# Block_Diagramme.net
KiCad netlist of a schematic drawn in Altium Designer
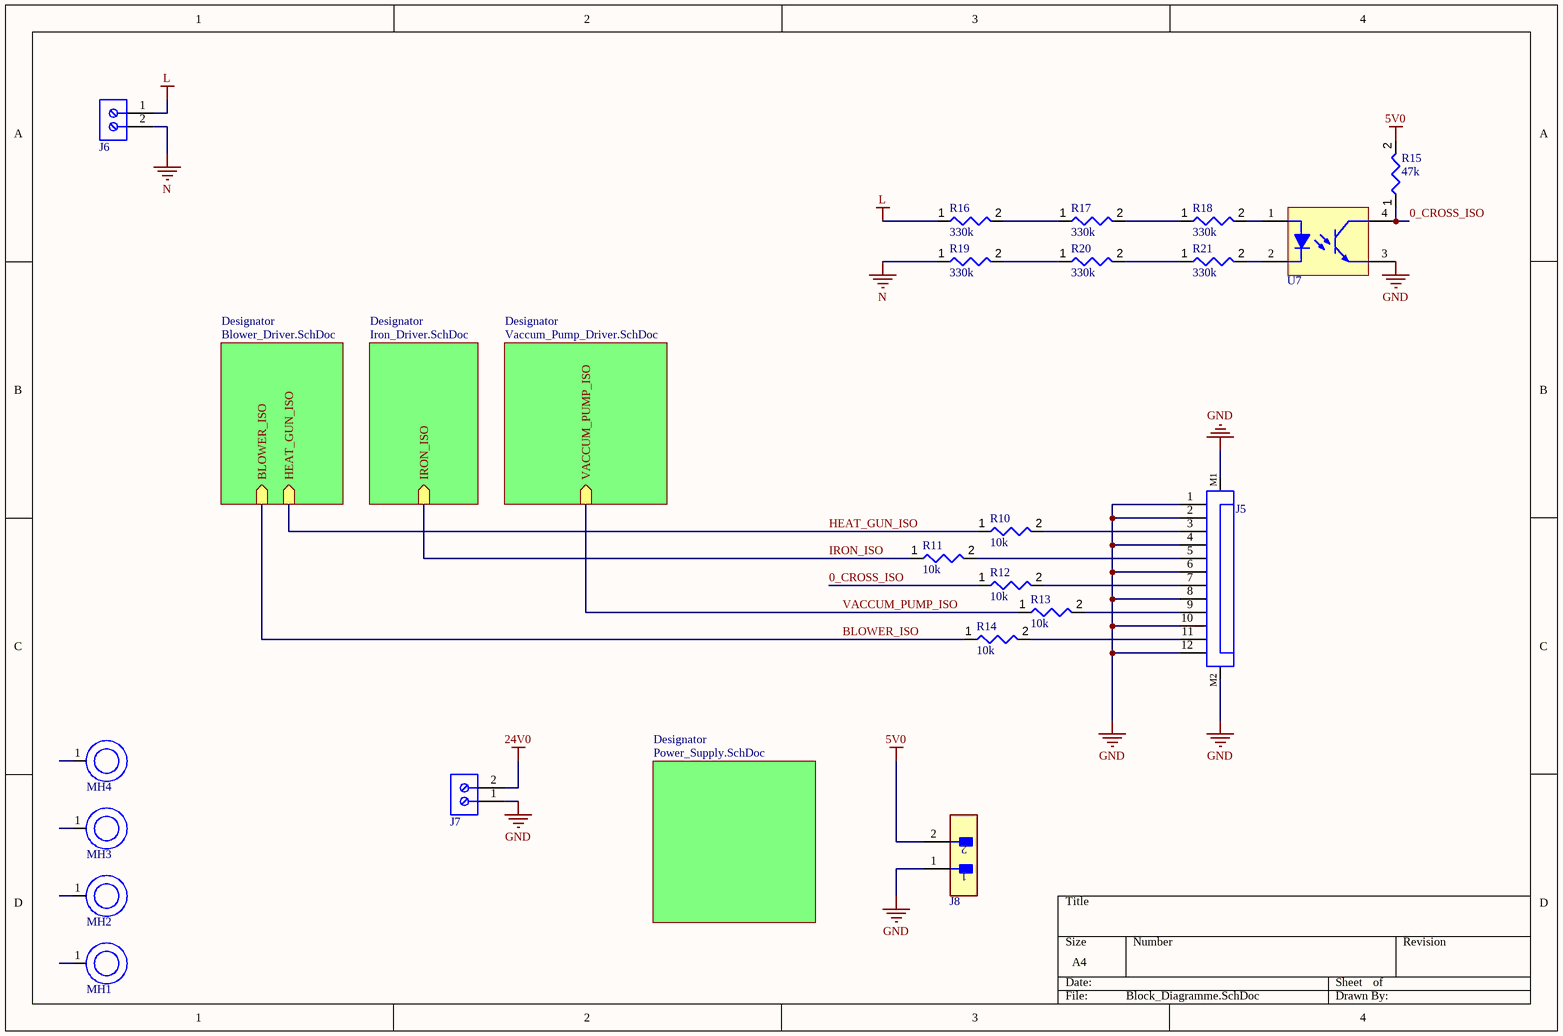
[diagram p0: Block_Diagramme.SchDoc]

(export (version "E")
  (design (tool "Eeschema 10.0.6"))
  (components
    (comp (ref "J5")
      (value "687112183622")
      (footprint "687112183622")
      (libsource (lib "Altium Content Vault") (part "FPC - 12P - 2MP"))
    )
    (comp (ref "J6")
      (value "691137710002")
      (footprint "691137710002")
      (description "2P Block Terminal")
      (libsource (lib "Paulo Peixoto") (part "Generic_2P_Block_Terminal"))
    )
    (comp (ref "J7")
      (value "691137710002")
      (footprint "691137710002")
      (description "2P Block Terminal")
      (libsource (lib "Paulo Peixoto") (part "Generic_2P_Block_Terminal"))
    )
    (comp (ref "J8")
      (value "B2B-XH-A(LF)(SN)")
      (footprint "FP-B2B-XH-A_LF_SN-MFG")
      (description "CONNECTOR HEADER, XH SERIES, 2 POSITION, 2.50MM, Press-Fit Solder, Detent Lock, Natural")
      (libsource (lib "Paulo Peixoto") (part "3bc925449376181038e59eaffc5286c"))
    )
    (comp (ref "MH1")
      (value "3mm_Mounting_Hole")
      (footprint "Single_3mm_Mounting_Hole")
      (description "3.2mm, sPad Mounting Hole")
      (libsource (lib "Paulo Peixoto") (part "Generic_Mounting_Hole"))
    )
    (comp (ref "MH2")
      (value "3mm_Mounting_Hole")
      (footprint "Single_3mm_Mounting_Hole")
      (description "3.2mm, sPad Mounting Hole")
      (libsource (lib "Paulo Peixoto") (part "Generic_Mounting_Hole"))
    )
    (comp (ref "MH3")
      (value "3mm_Mounting_Hole")
      (footprint "Single_3mm_Mounting_Hole")
      (description "3.2mm, sPad Mounting Hole")
      (libsource (lib "Paulo Peixoto") (part "Generic_Mounting_Hole"))
    )
    (comp (ref "MH4")
      (value "3mm_Mounting_Hole")
      (footprint "Single_3mm_Mounting_Hole")
      (description "3.2mm, sPad Mounting Hole")
      (libsource (lib "Paulo Peixoto") (part "Generic_Mounting_Hole"))
    )
    (comp (ref "R10")
      (value "10k")
      (footprint "Generic_0603_RES")
      (fields
        (field (name "TOLERANCE") "1%")
        (field (name "POWER") "100mW")
        (field (name "Comment") "RES-TK_SMD-0603_VIS-CRCW_K_10K_1/10W_1%")
      )
      (libsource (lib "Paulo Peixoto") (part "Res"))
    )
    (comp (ref "R11")
      (value "10k")
      (footprint "Generic_0603_RES")
      (fields
        (field (name "TOLERANCE") "1%")
        (field (name "POWER") "100mW")
        (field (name "Comment") "RES-TK_SMD-0603_VIS-CRCW_K_10K_1/10W_1%")
      )
      (libsource (lib "Paulo Peixoto") (part "Res"))
    )
    (comp (ref "R12")
      (value "10k")
      (footprint "Generic_0603_RES")
      (fields
        (field (name "TOLERANCE") "1%")
        (field (name "POWER") "100mW")
        (field (name "Comment") "RES-TK_SMD-0603_VIS-CRCW_K_10K_1/10W_1%")
      )
      (libsource (lib "Paulo Peixoto") (part "Res"))
    )
    (comp (ref "R13")
      (value "10k")
      (footprint "Generic_0603_RES")
      (fields
        (field (name "TOLERANCE") "1%")
        (field (name "POWER") "100mW")
        (field (name "Comment") "RES-TK_SMD-0603_VIS-CRCW_K_10K_1/10W_1%")
      )
      (libsource (lib "Paulo Peixoto") (part "Res"))
    )
    (comp (ref "R14")
      (value "10k")
      (footprint "Generic_0603_RES")
      (fields
        (field (name "TOLERANCE") "1%")
        (field (name "POWER") "100mW")
        (field (name "Comment") "RES-TK_SMD-0603_VIS-CRCW_K_10K_1/10W_1%")
      )
      (libsource (lib "Paulo Peixoto") (part "Res"))
    )
    (comp (ref "R15")
      (value "47k")
      (footprint "Generic_0603_RES")
      (fields
        (field (name "TOLERANCE") "1%")
        (field (name "POWER") "100mW")
        (field (name "Comment") "RES-TK_SMD-0603_VIS-CRCW_K_47K_1/10W_1%")
      )
      (libsource (lib "Paulo Peixoto") (part "Res"))
    )
    (comp (ref "R16")
      (value "330k")
      (footprint "Generic_1206_RES")
      (description "Res Thick Film 1206 330K Ohm 1% 1/4W ±100ppm/°C Molded SMD SMD Paper T/R")
      (fields (field (name "TOLERANCE") "1%") (field (name "POWER") "750mW"))
      (libsource (lib "Paulo Peixoto") (part "Res"))
    )
    (comp (ref "R17")
      (value "330k")
      (footprint "Generic_1206_RES")
      (description "Res Thick Film 1206 330K Ohm 1% 1/4W ±100ppm/°C Molded SMD SMD Paper T/R")
      (fields (field (name "TOLERANCE") "1%") (field (name "POWER") "750mW"))
      (libsource (lib "Paulo Peixoto") (part "Res"))
    )
    (comp (ref "R18")
      (value "330k")
      (footprint "Generic_1206_RES")
      (description "Res Thick Film 1206 330K Ohm 1% 1/4W ±100ppm/°C Molded SMD SMD Paper T/R")
      (fields (field (name "TOLERANCE") "1%") (field (name "POWER") "750mW"))
      (libsource (lib "Paulo Peixoto") (part "Res"))
    )
    (comp (ref "R19")
      (value "330k")
      (footprint "Generic_1206_RES")
      (description "Res Thick Film 1206 330K Ohm 1% 1/4W ±100ppm/°C Molded SMD SMD Paper T/R")
      (fields (field (name "TOLERANCE") "1%") (field (name "POWER") "750mW"))
      (libsource (lib "Paulo Peixoto") (part "Res"))
    )
    (comp (ref "R20")
      (value "330k")
      (footprint "Generic_1206_RES")
      (description "Res Thick Film 1206 330K Ohm 1% 1/4W ±100ppm/°C Molded SMD SMD Paper T/R")
      (fields (field (name "TOLERANCE") "1%") (field (name "POWER") "750mW"))
      (libsource (lib "Paulo Peixoto") (part "Res"))
    )
    (comp (ref "R21")
      (value "330k")
      (footprint "Generic_1206_RES")
      (description "Res Thick Film 1206 330K Ohm 1% 1/4W ±100ppm/°C Molded SMD SMD Paper T/R")
      (fields (field (name "TOLERANCE") "1%") (field (name "POWER") "750mW"))
      (libsource (lib "Paulo Peixoto") (part "Res"))
    )
    (comp (ref "U7")
      (value "H11A817ASD")
      (footprint "FAIR-H11A817ASD-4_V")
      (description "OptoCouplers & OptoIsolators Optocoupler SM-DIP4 Phototransistor")
      (libsource (lib "Paulo Peixoto") (part "FAIR-H11A817-4"))
    )
  )
  (nets
    (net (code "1") (name "/0_CROSS_ISO") (class "Default")
      (node (ref "R12") (pin "1") (pinfunction "1_1") (pintype "passive"))
      (node (ref "R15") (pin "1") (pinfunction "1_1") (pintype "passive"))
      (node (ref "U7") (pin "4") (pinfunction "COLLECTOR_4") (pintype "passive"))
    )
    (net (code "2") (name "/BLOWER_ISO") (class "Default")
      (node (ref "R14") (pin "1") (pinfunction "1_1") (pintype "passive"))
    )
    (net (code "3") (name "/HEAT_GUN_ISO") (class "Default")
      (node (ref "R10") (pin "1") (pinfunction "1_1") (pintype "passive"))
    )
    (net (code "4") (name "/IRON_ISO") (class "Default")
      (node (ref "R11") (pin "1") (pinfunction "1_1") (pintype "passive"))
    )
    (net (code "5") (name "/VACCUM_PUMP_ISO") (class "Default")
      (node (ref "R13") (pin "1") (pinfunction "1_1") (pintype "passive"))
    )
    (net (code "6") (name "5V0") (class "Default")
      (node (ref "J8") (pin "2") (pinfunction "2_2") (pintype "passive"))
      (node (ref "R15") (pin "2") (pinfunction "2_2") (pintype "passive"))
    )
    (net (code "7") (name "24V0") (class "Default")
      (node (ref "J7") (pin "2") (pinfunction "2_2") (pintype "passive"))
    )
    (net (code "8") (name "GND") (class "Default")
      (node (ref "J5") (pin "1") (pinfunction "1_1") (pintype "passive"))
      (node (ref "J5") (pin "10") (pinfunction "10_10") (pintype "passive"))
      (node (ref "J5") (pin "12") (pinfunction "12_12") (pintype "passive"))
      (node (ref "J5") (pin "2") (pinfunction "2_2") (pintype "passive"))
      (node (ref "J5") (pin "4") (pinfunction "4_4") (pintype "passive"))
      (node (ref "J5") (pin "6") (pinfunction "6_6") (pintype "passive"))
      (node (ref "J5") (pin "8") (pinfunction "8_8") (pintype "passive"))
      (node (ref "J5") (pin "M1") (pinfunction "M1_M1") (pintype "passive"))
      (node (ref "J5") (pin "M2") (pinfunction "M2_M2") (pintype "passive"))
      (node (ref "J7") (pin "1") (pinfunction "1_1") (pintype "passive"))
      (node (ref "J8") (pin "1") (pinfunction "1_1") (pintype "passive"))
      (node (ref "U7") (pin "3") (pinfunction "EMITTER_3") (pintype "passive"))
    )
    (net (code "9") (name "L") (class "Default")
      (node (ref "J6") (pin "1") (pinfunction "1_1") (pintype "passive"))
      (node (ref "R16") (pin "1") (pinfunction "1_1") (pintype "passive"))
    )
    (net (code "10") (name "N") (class "Default")
      (node (ref "J6") (pin "2") (pinfunction "2_2") (pintype "passive"))
      (node (ref "R19") (pin "1") (pinfunction "1_1") (pintype "passive"))
    )
    (net (code "11") (name "Net-(J5-Pad3)") (class "Default")
      (node (ref "J5") (pin "3") (pinfunction "3_3") (pintype "passive"))
      (node (ref "R10") (pin "2") (pinfunction "2_2") (pintype "passive"))
    )
    (net (code "12") (name "Net-(J5-Pad5)") (class "Default")
      (node (ref "J5") (pin "5") (pinfunction "5_5") (pintype "passive"))
      (node (ref "R11") (pin "2") (pinfunction "2_2") (pintype "passive"))
    )
    (net (code "13") (name "Net-(J5-Pad7)") (class "Default")
      (node (ref "J5") (pin "7") (pinfunction "7_7") (pintype "passive"))
      (node (ref "R12") (pin "2") (pinfunction "2_2") (pintype "passive"))
    )
    (net (code "14") (name "Net-(J5-Pad9)") (class "Default")
      (node (ref "J5") (pin "9") (pinfunction "9_9") (pintype "passive"))
      (node (ref "R13") (pin "2") (pinfunction "2_2") (pintype "passive"))
    )
    (net (code "15") (name "Net-(J5-Pad11)") (class "Default")
      (node (ref "J5") (pin "11") (pinfunction "11_11") (pintype "passive"))
      (node (ref "R14") (pin "2") (pinfunction "2_2") (pintype "passive"))
    )
    (net (code "16") (name "Net-(R16-Pad2)") (class "Default")
      (node (ref "R16") (pin "2") (pinfunction "2_2") (pintype "passive"))
      (node (ref "R17") (pin "1") (pinfunction "1_1") (pintype "passive"))
    )
    (net (code "17") (name "Net-(R17-Pad2)") (class "Default")
      (node (ref "R17") (pin "2") (pinfunction "2_2") (pintype "passive"))
      (node (ref "R18") (pin "1") (pinfunction "1_1") (pintype "passive"))
    )
    (net (code "18") (name "Net-(R19-Pad2)") (class "Default")
      (node (ref "R19") (pin "2") (pinfunction "2_2") (pintype "passive"))
      (node (ref "R20") (pin "1") (pinfunction "1_1") (pintype "passive"))
    )
    (net (code "19") (name "Net-(R20-Pad2)") (class "Default")
      (node (ref "R20") (pin "2") (pinfunction "2_2") (pintype "passive"))
      (node (ref "R21") (pin "1") (pinfunction "1_1") (pintype "passive"))
    )
    (net (code "20") (name "Net-(U7-ANODE)") (class "Default")
      (node (ref "R18") (pin "2") (pinfunction "2_2") (pintype "passive"))
      (node (ref "U7") (pin "1") (pinfunction "ANODE_1") (pintype "passive"))
    )
    (net (code "21") (name "Net-(U7-CATHODE)") (class "Default")
      (node (ref "R21") (pin "2") (pinfunction "2_2") (pintype "passive"))
      (node (ref "U7") (pin "2") (pinfunction "CATHODE_2") (pintype "passive"))
    )
    (net (code "22") (name "unconnected-(MH1-Pad1)") (class "Default")
      (node (ref "MH1") (pin "1") (pinfunction "1_1") (pintype "passive"))
    )
    (net (code "23") (name "unconnected-(MH2-Pad1)") (class "Default")
      (node (ref "MH2") (pin "1") (pinfunction "1_1") (pintype "passive"))
    )
    (net (code "24") (name "unconnected-(MH3-Pad1)") (class "Default")
      (node (ref "MH3") (pin "1") (pinfunction "1_1") (pintype "passive"))
    )
    (net (code "25") (name "unconnected-(MH4-Pad1)") (class "Default")
      (node (ref "MH4") (pin "1") (pinfunction "1_1") (pintype "passive"))
    )
  )
)
